# inktime.net
KiCad netlist of a schematic drawn in EAGLE
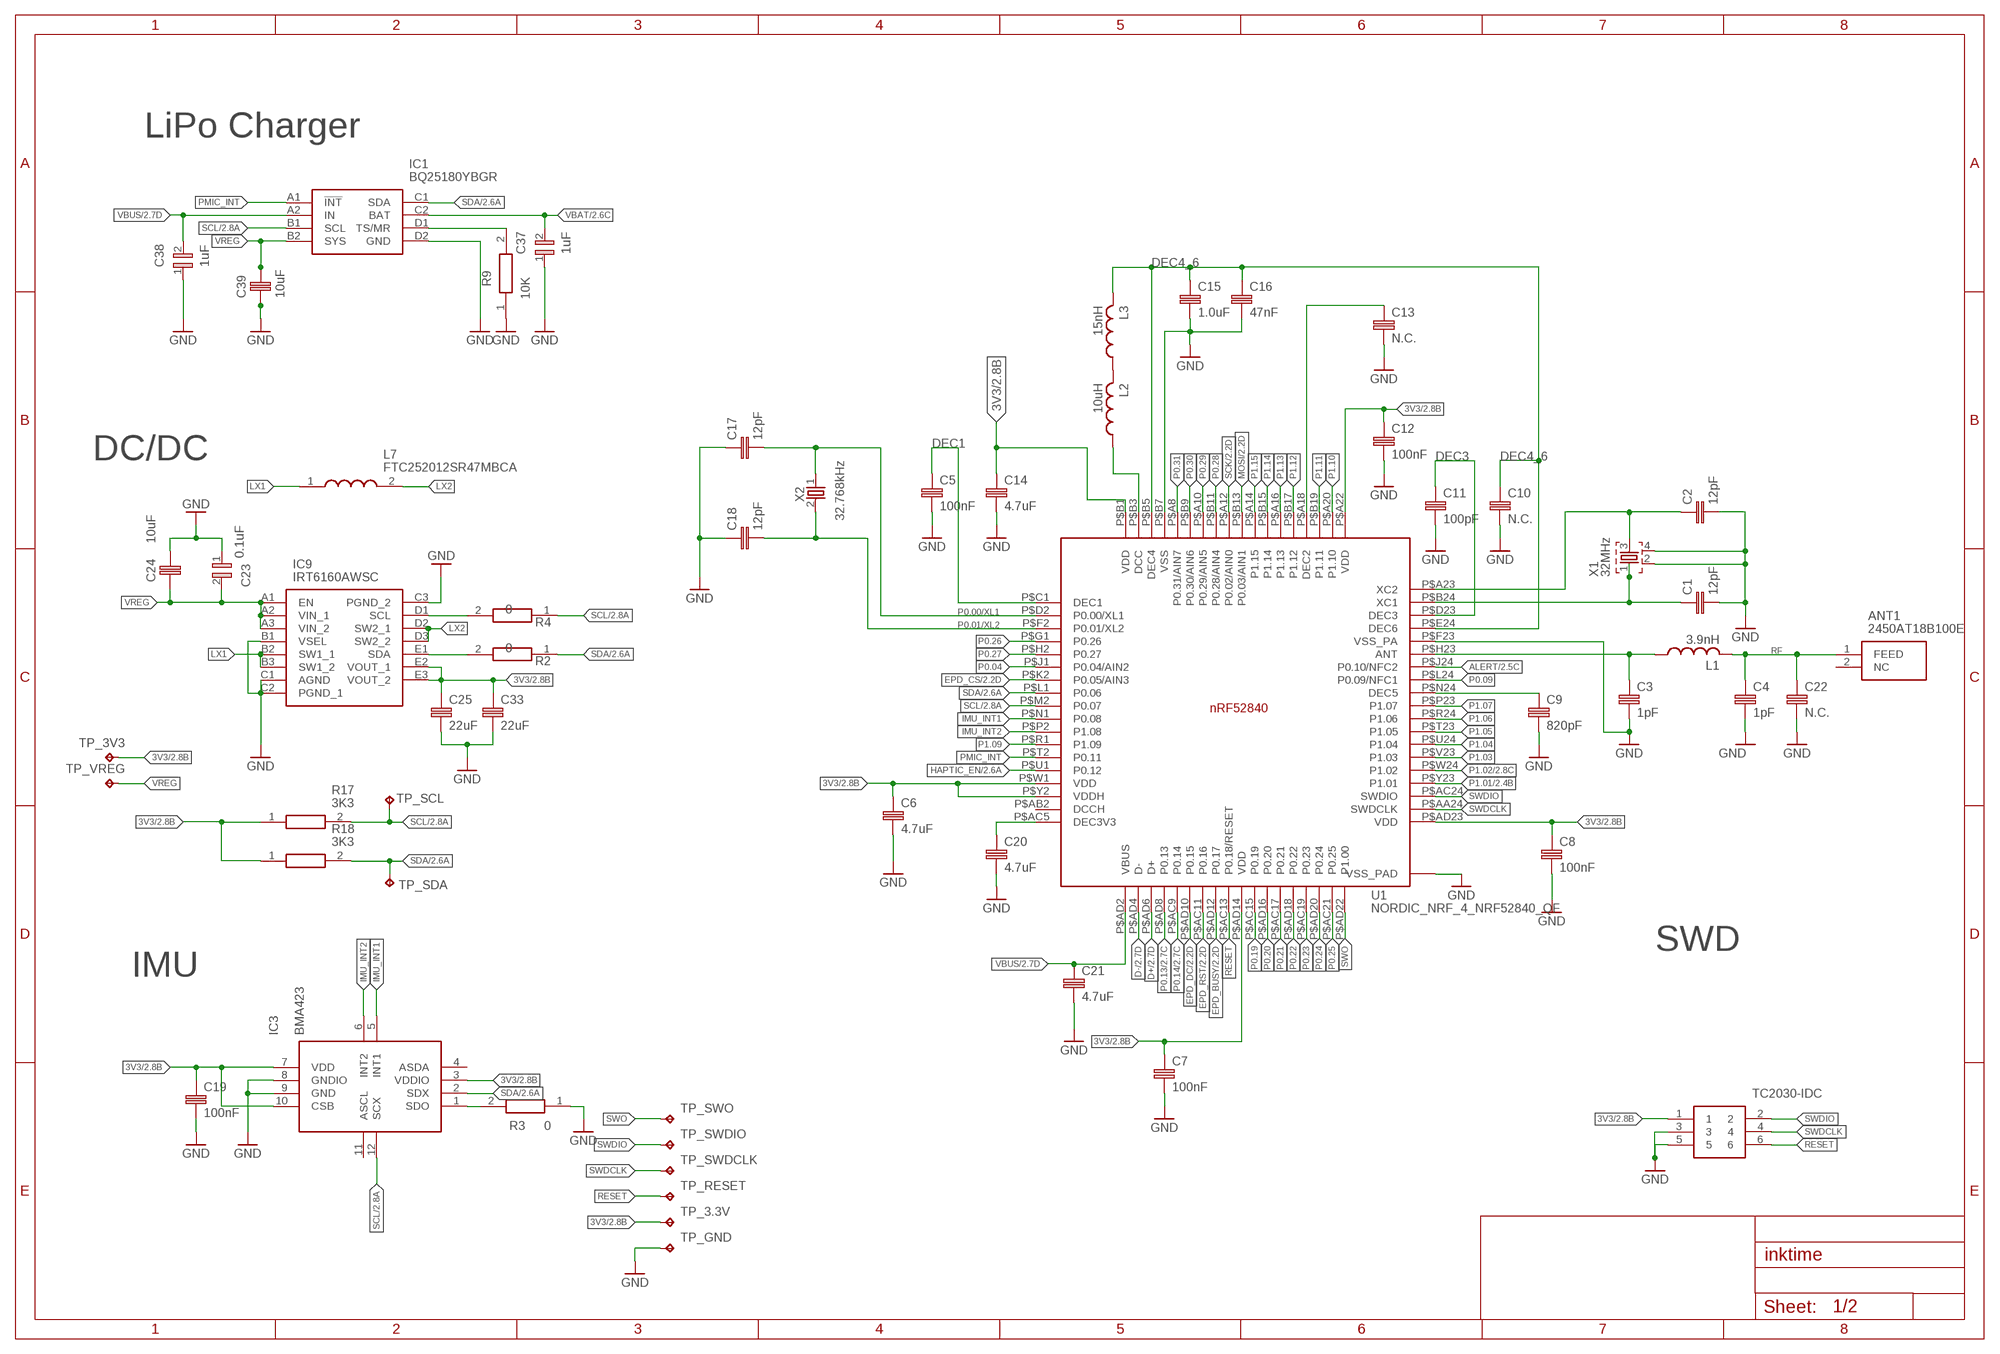
[diagram p0: schematic, sheet 1]
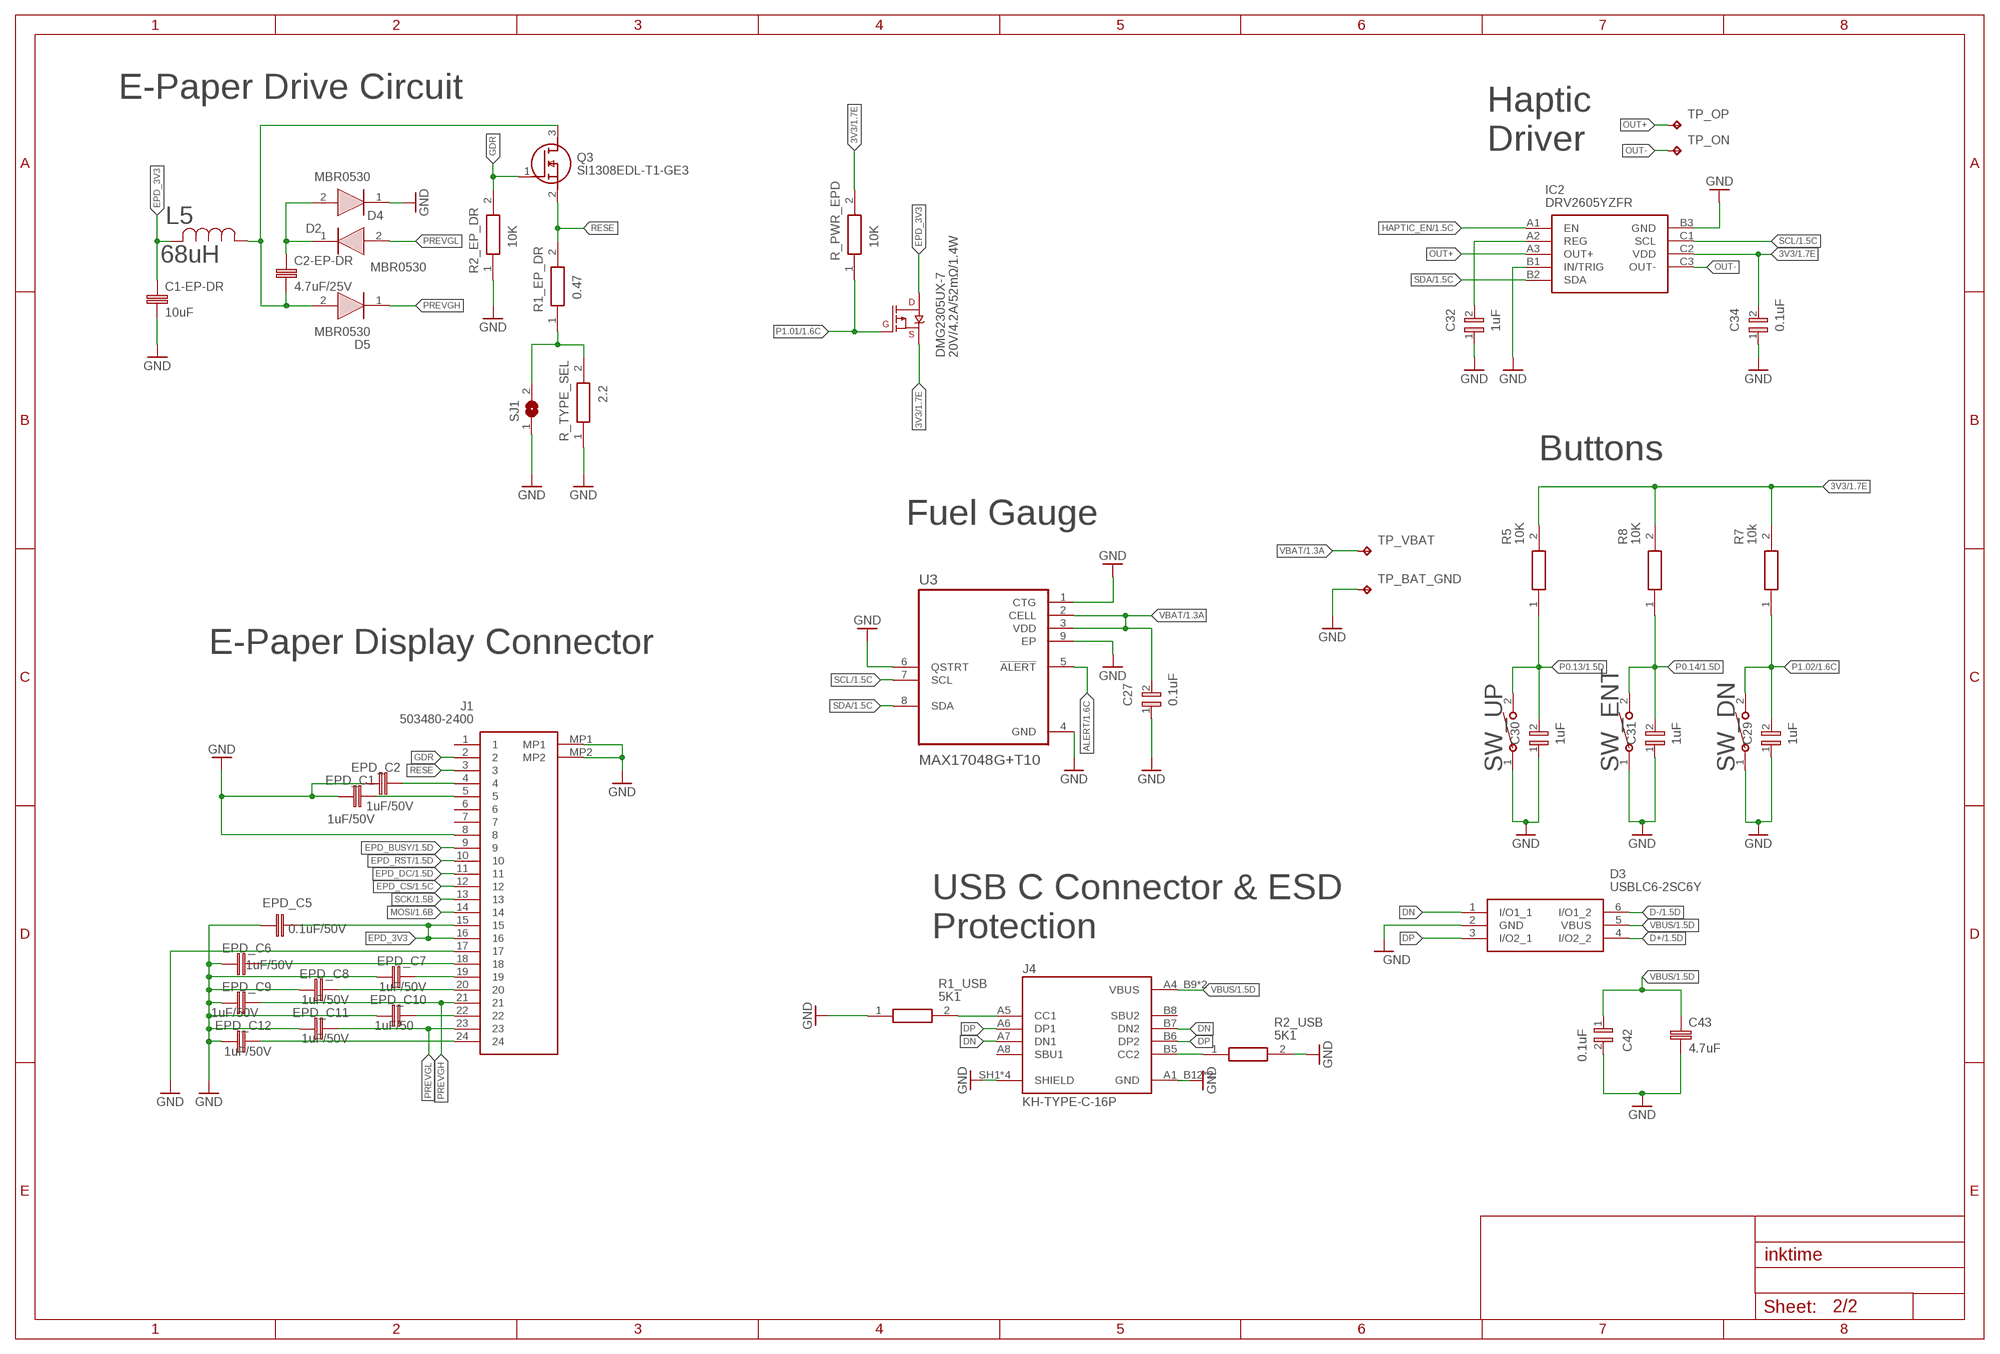
[diagram p1: schematic, sheet 2]

(export (version "E")
  (design (tool "Eeschema 10.0.6"))
  (components
    (comp (ref "ANT1")
      (value "2450AT18B100E")
      (footprint "eagle-import:2450AT18B100E_ANTC3216X140N")
      (fields (field (name "MOUSER_PART_NUMBER") "609-2450AT18B100E"))
      (libsource (lib "eagle-import") (part "2450AT18B100E_2450AT18B100E"))
    )
    (comp (ref "C1")
      (value "12pF")
      (footprint "eagle-import:NORDIC_NRF_3_RESC0201_L")
      (libsource (lib "eagle-import") (part "NORDIC_NRF_3_CAPACITOR_0201_L"))
    )
    (comp (ref "C2")
      (value "12pF")
      (footprint "eagle-import:NORDIC_NRF_3_RESC0201_L")
      (libsource (lib "eagle-import") (part "NORDIC_NRF_3_CAPACITOR_0201_L"))
    )
    (comp (ref "C3")
      (value "1pF")
      (footprint "eagle-import:NORDIC_NRF_3_RESC0201_L")
      (libsource (lib "eagle-import") (part "NORDIC_NRF_3_CAPACITOR_0201_L"))
    )
    (comp (ref "C4")
      (value "1pF")
      (footprint "eagle-import:NORDIC_NRF_3_RESC0201_L")
      (libsource (lib "eagle-import") (part "NORDIC_NRF_3_CAPACITOR_0201_L"))
    )
    (comp (ref "C5")
      (value "100nF")
      (footprint "eagle-import:NORDIC_NRF_3_RESC0201_L")
      (libsource (lib "eagle-import") (part "NORDIC_NRF_3_CAPACITOR_0201_L"))
    )
    (comp (ref "C6")
      (value "4.7uF")
      (footprint "eagle-import:NORDIC_NRF_3_RESC0402_L")
      (libsource (lib "eagle-import") (part "NORDIC_NRF_3_CAPACITOR_0402_L"))
    )
    (comp (ref "C7")
      (value "100nF")
      (footprint "eagle-import:NORDIC_NRF_3_RESC0201_L")
      (libsource (lib "eagle-import") (part "NORDIC_NRF_3_CAPACITOR_0201_L"))
    )
    (comp (ref "C8")
      (value "100nF")
      (footprint "eagle-import:NORDIC_NRF_3_RESC0201_L")
      (libsource (lib "eagle-import") (part "NORDIC_NRF_3_CAPACITOR_0201_L"))
    )
    (comp (ref "C9")
      (value "820pF")
      (footprint "eagle-import:NORDIC_NRF_3_RESC0201_L")
      (libsource (lib "eagle-import") (part "NORDIC_NRF_3_CAPACITOR_0201_L"))
    )
    (comp (ref "C10")
      (value "N.C.")
      (footprint "eagle-import:NORDIC_NRF_3_RESC0201_L")
      (libsource (lib "eagle-import") (part "NORDIC_NRF_3_CAPACITOR_0201_L"))
    )
    (comp (ref "C11")
      (value "100pF")
      (footprint "eagle-import:NORDIC_NRF_3_RESC0201_L")
      (libsource (lib "eagle-import") (part "NORDIC_NRF_3_CAPACITOR_0201_L"))
    )
    (comp (ref "C12")
      (value "100nF")
      (footprint "eagle-import:NORDIC_NRF_3_RESC0201_L")
      (libsource (lib "eagle-import") (part "NORDIC_NRF_3_CAPACITOR_0201_L"))
    )
    (comp (ref "C13")
      (value "N.C.")
      (footprint "eagle-import:NORDIC_NRF_3_RESC0201_L")
      (libsource (lib "eagle-import") (part "NORDIC_NRF_3_CAPACITOR_0201_L"))
    )
    (comp (ref "C14")
      (value "4.7uF")
      (footprint "eagle-import:NORDIC_NRF_3_RESC0402_L")
      (libsource (lib "eagle-import") (part "NORDIC_NRF_3_CAPACITOR_0402_L"))
    )
    (comp (ref "C15")
      (value "1.0uF")
      (footprint "eagle-import:NORDIC_NRF_3_RESC0402_L")
      (libsource (lib "eagle-import") (part "NORDIC_NRF_3_CAPACITOR_0402_L"))
    )
    (comp (ref "C16")
      (value "47nF")
      (footprint "eagle-import:NORDIC_NRF_3_RESC0201_L")
      (libsource (lib "eagle-import") (part "NORDIC_NRF_3_CAPACITOR_0201_L"))
    )
    (comp (ref "C17")
      (value "12pF")
      (footprint "eagle-import:NORDIC_NRF_3_RESC0201_L")
      (libsource (lib "eagle-import") (part "NORDIC_NRF_3_CAPACITOR_0201_L"))
    )
    (comp (ref "C18")
      (value "12pF")
      (footprint "eagle-import:NORDIC_NRF_3_RESC0201_L")
      (libsource (lib "eagle-import") (part "NORDIC_NRF_3_CAPACITOR_0201_L"))
    )
    (comp (ref "C19")
      (value "100nF")
      (footprint "eagle-import:NORDIC_NRF_3_RESC0201_L")
      (libsource (lib "eagle-import") (part "NORDIC_NRF_3_CAPACITOR_0201_L"))
    )
    (comp (ref "C20")
      (value "4.7uF")
      (footprint "eagle-import:NORDIC_NRF_3_RESC0402_L")
      (libsource (lib "eagle-import") (part "NORDIC_NRF_3_CAPACITOR_0402_L"))
    )
    (comp (ref "C21")
      (value "4.7uF")
      (footprint "eagle-import:NORDIC_NRF_3_RESC0402_L")
      (libsource (lib "eagle-import") (part "NORDIC_NRF_3_CAPACITOR_0402_L"))
    )
    (comp (ref "C22")
      (value "N.C.")
      (footprint "eagle-import:NORDIC_NRF_3_RESC0201_L")
      (libsource (lib "eagle-import") (part "NORDIC_NRF_3_CAPACITOR_0201_L"))
    )
    (comp (ref "C23")
      (value "0.1uF")
      (footprint "eagle-import:GRM011R60J152KE01L_2_CAPC0201X13N")
      (fields (field (name "MF") "Murata") (field (name "MP") "GRM011R60J152KE01L"))
      (libsource (lib "eagle-import") (part "GRM011R60J152KE01L_2_GRM011R60J152KE01L"))
    )
    (comp (ref "C24")
      (value "10uF")
      (footprint "eagle-import:NORDIC_NRF_3_RESC0402_L")
      (libsource (lib "eagle-import") (part "NORDIC_NRF_3_CAPACITOR_0402_L"))
    )
    (comp (ref "C25")
      (value "22uF")
      (footprint "eagle-import:NORDIC_NRF_3_RESC0402_L")
      (libsource (lib "eagle-import") (part "NORDIC_NRF_3_CAPACITOR_0402_L"))
    )
    (comp (ref "C33")
      (value "22uF")
      (footprint "eagle-import:NORDIC_NRF_3_RESC0402_L")
      (libsource (lib "eagle-import") (part "NORDIC_NRF_3_CAPACITOR_0402_L"))
    )
    (comp (ref "C37")
      (value "1uF")
      (footprint "eagle-import:GRM011R60J152KE01L_2_CAPC0201X13N")
      (fields (field (name "MF") "Murata") (field (name "MP") "GRM011R60J152KE01L"))
      (libsource (lib "eagle-import") (part "GRM011R60J152KE01L_2_GRM011R60J152KE01L"))
    )
    (comp (ref "C38")
      (value "1uF")
      (footprint "eagle-import:GRM011R60J152KE01L_2_CAPC0201X13N")
      (fields (field (name "MF") "Murata") (field (name "MP") "GRM011R60J152KE01L"))
      (libsource (lib "eagle-import") (part "GRM011R60J152KE01L_2_GRM011R60J152KE01L"))
    )
    (comp (ref "C39")
      (value "10uF")
      (footprint "eagle-import:NORDIC_NRF_3_RESC0402_L")
      (libsource (lib "eagle-import") (part "NORDIC_NRF_3_CAPACITOR_0402_L"))
    )
    (comp (ref "IC1")
      (value "BQ25180YBGR")
      (footprint "eagle-import:BQ25180YBGR_BGA8C40P2X4_100X155X50")
      (fields (field (name "MOUSER_PART_NUMBER") "595-BQ25180YBGR"))
      (libsource (lib "eagle-import") (part "BQ25180YBGR_BQ25180YBGR"))
    )
    (comp (ref "IC3")
      (value "BMA423")
      (footprint "eagle-import:BMA423_BMA423")
      (fields (field (name "MOUSER_PART_NUMBER") "262-BMA423"))
      (libsource (lib "eagle-import") (part "BMA423_BMA423"))
    )
    (comp (ref "IC9")
      (value "IRT6160AWSC")
      (footprint "eagle-import:RT6160AWSC_BGA15C40P3X5_140X230X60")
      (fields
        (field (name "MANUFACTURER_PART_NUMBER") "RT6160AWSC")
        (field (name "MOUSER_PART_NUMBER") "835-RT6160AWSC")
      )
      (libsource (lib "eagle-import") (part "RT6160AWSC_RT6160AWSC"))
    )
    (comp (ref "J2")
      (value "TC2030-IDC")
      (footprint "eagle-import:TC2030-IDC_TC2030IDC")
      (libsource (lib "eagle-import") (part "TC2030-IDC_TC2030-IDC"))
    )
    (comp (ref "L1")
      (value "3.9nH")
      (footprint "eagle-import:NORDIC_NRF_2_RESC0402_L")
      (libsource (lib "eagle-import") (part "NORDIC_NRF_2_INDUCTOR_0402_L"))
    )
    (comp (ref "L2")
      (value "10uH")
      (footprint "eagle-import:NORDIC_NRF_2_RESC0402_L")
      (libsource (lib "eagle-import") (part "NORDIC_NRF_2_INDUCTOR_0402_L"))
    )
    (comp (ref "L3")
      (value "15nH")
      (footprint "eagle-import:NORDIC_NRF_2_RESC0402_L")
      (libsource (lib "eagle-import") (part "NORDIC_NRF_2_INDUCTOR_0402_L"))
    )
    (comp (ref "L7")
      (value "FTC252012SR47MBCA")
      (footprint "eagle-import:MLP2016SR47MT0S1_INDC2016X100N")
      (libsource (lib "eagle-import") (part "MLP2016SR47MT0S1_FTC252012SR47MBCA"))
    )
    (comp (ref "R2")
      (value "0")
      (footprint "eagle-import:ERA-1AEB3401C_0201")
      (libsource (lib "eagle-import") (part "ERA-1AEB3401C_CPF0201D7K68C1"))
    )
    (comp (ref "R3")
      (value "0")
      (footprint "eagle-import:CPF0201D7K68C1_0201")
      (libsource (lib "eagle-import") (part "CPF0201D7K68C1_CPF0201D7K68C1"))
    )
    (comp (ref "R4")
      (value "0")
      (footprint "eagle-import:ERA-1AEB3401C_0201")
      (libsource (lib "eagle-import") (part "ERA-1AEB3401C_CPF0201D7K68C1"))
    )
    (comp (ref "R9")
      (value "10K")
      (footprint "eagle-import:ERA-1AEB3401C_0201")
      (libsource (lib "eagle-import") (part "ERA-1AEB3401C_CPF0201D7K68C1"))
    )
    (comp (ref "R17")
      (value "3K3")
      (footprint "eagle-import:CPF0201D7K68C1_0201")
      (libsource (lib "eagle-import") (part "CPF0201D7K68C1_CPF0201D7K68C1"))
    )
    (comp (ref "R18")
      (value "3K3")
      (footprint "eagle-import:CPF0201D7K68C1_0201")
      (libsource (lib "eagle-import") (part "CPF0201D7K68C1_CPF0201D7K68C1"))
    )
    (comp (ref "TP_3.3V")
      (value "HECTOR_WATCH_1_TPTP20R")
      (footprint "eagle-import:HECTOR_WATCH_1_TP20R")
      (libsource (lib "eagle-import") (part "HECTOR_WATCH_1_TPTP20R"))
    )
    (comp (ref "TP_3V3")
      (value "HECTOR_WATCH_1_TPTP20R")
      (footprint "eagle-import:HECTOR_WATCH_1_TP20R")
      (libsource (lib "eagle-import") (part "HECTOR_WATCH_1_TPTP20R"))
    )
    (comp (ref "TP_GND")
      (value "HECTOR_WATCH_1_TPTP20R")
      (footprint "eagle-import:HECTOR_WATCH_1_TP20R")
      (libsource (lib "eagle-import") (part "HECTOR_WATCH_1_TPTP20R"))
    )
    (comp (ref "TP_RESET")
      (value "HECTOR_WATCH_1_TPTP20R")
      (footprint "eagle-import:HECTOR_WATCH_1_TP20R")
      (libsource (lib "eagle-import") (part "HECTOR_WATCH_1_TPTP20R"))
    )
    (comp (ref "TP_SCL")
      (value "HECTOR_WATCH_1_TPTP20R")
      (footprint "eagle-import:HECTOR_WATCH_1_TP20R")
      (libsource (lib "eagle-import") (part "HECTOR_WATCH_1_TPTP20R"))
    )
    (comp (ref "TP_SDA")
      (value "HECTOR_WATCH_1_TPTP20R")
      (footprint "eagle-import:HECTOR_WATCH_1_TP20R")
      (libsource (lib "eagle-import") (part "HECTOR_WATCH_1_TPTP20R"))
    )
    (comp (ref "TP_SWDCLK")
      (value "HECTOR_WATCH_1_TPTP20R")
      (footprint "eagle-import:HECTOR_WATCH_1_TP20R")
      (libsource (lib "eagle-import") (part "HECTOR_WATCH_1_TPTP20R"))
    )
    (comp (ref "TP_SWDIO")
      (value "HECTOR_WATCH_1_TPTP20R")
      (footprint "eagle-import:HECTOR_WATCH_1_TP20R")
      (libsource (lib "eagle-import") (part "HECTOR_WATCH_1_TPTP20R"))
    )
    (comp (ref "TP_SWO")
      (value "HECTOR_WATCH_1_TPTP20R")
      (footprint "eagle-import:HECTOR_WATCH_1_TP20R")
      (libsource (lib "eagle-import") (part "HECTOR_WATCH_1_TPTP20R"))
    )
    (comp (ref "TP_VREG")
      (value "HECTOR_WATCH_1_TPTP20R")
      (footprint "eagle-import:HECTOR_WATCH_1_TP20R")
      (libsource (lib "eagle-import") (part "HECTOR_WATCH_1_TPTP20R"))
    )
    (comp (ref "U$3")
      (value "NORDIC_NRF_3_CAPACITOR_0402_L")
      (footprint "eagle-import:NORDIC_NRF_3_RESC0402_L")
      (libsource (lib "eagle-import") (part "NORDIC_NRF_3_CAPACITOR_0402_L"))
    )
    (comp (ref "U1")
      (value "NORDIC_NRF_4_NRF52840_QF")
      (footprint "eagle-import:NORDIC_NRF_4_AQFN50P700X700X85_HS-74N")
      (libsource (lib "eagle-import") (part "NORDIC_NRF_4_NRF52840_QF"))
    )
    (comp (ref "X1")
      (value "32MHz")
      (footprint "eagle-import:NORDIC_NRF_BT-XTAL_2016_N")
      (libsource (lib "eagle-import") (part "NORDIC_NRF_XTAL_32MHZ"))
    )
    (comp (ref "X2")
      (value "32.768kHz")
      (footprint "eagle-import:NORDIC_NRF_1_XTAL_3215_N")
      (libsource (lib "eagle-import") (part "NORDIC_NRF_1_XTAL_32KHZ"))
    )
    (comp (ref "C1-EP-DR")
      (value "10uF")
      (footprint "eagle-import:NORDIC_NRF_3_RESC0402_L")
      (libsource (lib "eagle-import") (part "NORDIC_NRF_3_CAPACITOR_0402_L"))
    )
    (comp (ref "C2-EP-DR")
      (value "4.7uF/25V")
      (footprint "eagle-import:NORDIC_NRF_3_RESC0402_L")
      (libsource (lib "eagle-import") (part "NORDIC_NRF_3_CAPACITOR_0402_L"))
    )
    (comp (ref "C27")
      (value "0.1uF")
      (footprint "eagle-import:GRM011R60J152KE01L_2_CAPC0201X13N")
      (fields (field (name "MF") "Murata") (field (name "MP") "GRM011R60J152KE01L"))
      (libsource (lib "eagle-import") (part "GRM011R60J152KE01L_2_GRM011R60J152KE01L"))
    )
    (comp (ref "C29")
      (value "1uF")
      (footprint "eagle-import:GRM011R60J152KE01L_2_CAPC0201X13N")
      (fields (field (name "MF") "Murata") (field (name "MP") "GRM011R60J152KE01L"))
      (libsource (lib "eagle-import") (part "GRM011R60J152KE01L_2_GRM011R60J152KE01L"))
    )
    (comp (ref "C30")
      (value "1uF")
      (footprint "eagle-import:GRM011R60J152KE01L_2_CAPC0201X13N")
      (fields (field (name "MF") "Murata") (field (name "MP") "GRM011R60J152KE01L"))
      (libsource (lib "eagle-import") (part "GRM011R60J152KE01L_2_GRM011R60J152KE01L"))
    )
    (comp (ref "C31")
      (value "1uF")
      (footprint "eagle-import:GRM011R60J152KE01L_2_CAPC0201X13N")
      (fields (field (name "MF") "Murata") (field (name "MP") "GRM011R60J152KE01L"))
      (libsource (lib "eagle-import") (part "GRM011R60J152KE01L_2_GRM011R60J152KE01L"))
    )
    (comp (ref "C32")
      (value "1uF")
      (footprint "eagle-import:GRM011R60J152KE01L_2_CAPC0201X13N")
      (fields (field (name "MF") "Murata") (field (name "MP") "GRM011R60J152KE01L"))
      (libsource (lib "eagle-import") (part "GRM011R60J152KE01L_2_GRM011R60J152KE01L"))
    )
    (comp (ref "C34")
      (value "0.1uF")
      (footprint "eagle-import:GRM011R60J152KE01L_2_CAPC0201X13N")
      (fields (field (name "MF") "Murata") (field (name "MP") "GRM011R60J152KE01L"))
      (libsource (lib "eagle-import") (part "GRM011R60J152KE01L_2_GRM011R60J152KE01L"))
    )
    (comp (ref "C42")
      (value "0.1uF")
      (footprint "eagle-import:GRM011R60J152KE01L_2_CAPC0201X13N")
      (fields (field (name "MF") "Murata") (field (name "MP") "GRM011R60J152KE01L"))
      (libsource (lib "eagle-import") (part "GRM011R60J152KE01L_2_GRM011R60J152KE01L"))
    )
    (comp (ref "C43")
      (value "4.7uF")
      (footprint "eagle-import:NORDIC_NRF_3_RESC0402_L")
      (libsource (lib "eagle-import") (part "NORDIC_NRF_3_CAPACITOR_0402_L"))
    )
    (comp (ref "D2")
      (value "MBR0530")
      (footprint "eagle-import:ESP32_C6_LIBRARY_5_SOD3716X135N")
      (fields (field (name "MF") "ON Semiconductor"))
      (libsource (lib "eagle-import") (part "ESP32_C6_LIBRARY_5_MBR0530"))
    )
    (comp (ref "D3")
      (value "USBLC6-2SC6Y")
      (footprint "eagle-import:ESP32_C6_LIBRARY_3_SOT95P280X145-6N")
      (fields (field (name "MF") "STMicroelectronics"))
      (libsource (lib "eagle-import") (part "ESP32_C6_LIBRARY_3_USBLC6-2SC6Y"))
    )
    (comp (ref "D4")
      (value "MBR0530")
      (footprint "eagle-import:ESP32_C6_LIBRARY_5_SOD3716X135N")
      (fields (field (name "MF") "ON Semiconductor"))
      (libsource (lib "eagle-import") (part "ESP32_C6_LIBRARY_5_MBR0530"))
    )
    (comp (ref "D5")
      (value "MBR0530")
      (footprint "eagle-import:ESP32_C6_LIBRARY_5_SOD3716X135N")
      (fields (field (name "MF") "ON Semiconductor"))
      (libsource (lib "eagle-import") (part "ESP32_C6_LIBRARY_5_MBR0530"))
    )
    (comp (ref "DMG2305UX-7")
      (value "20V/4.2A/52mΩ/1.4W")
      (footprint "eagle-import:ESP32_C6_LIBRARY_4_ESP32_C6_LIBRARY_4_ESP32_C6_LIBRARY_4_ESP32_C6_LIBRARY_4_ESP32_WROVER_SPARKFUN-DISCRETESEMI_SOT23-3")
      (libsource (lib "eagle-import") (part "ESP32_C6_LIBRARY_4_ESP32_WROVER_SPARKFUN-DISCRETESEMI_MOSFET_PCH-DMG2305UX-7"))
    )
    (comp (ref "EPD_C1")
      (value "1uF/50V")
      (footprint "eagle-import:NORDIC_NRF_3_RESC0402_L")
      (libsource (lib "eagle-import") (part "NORDIC_NRF_3_CAPACITOR_0402_L"))
    )
    (comp (ref "EPD_C2")
      (value "1uF/50V")
      (footprint "eagle-import:NORDIC_NRF_3_RESC0402_L")
      (libsource (lib "eagle-import") (part "NORDIC_NRF_3_CAPACITOR_0402_L"))
    )
    (comp (ref "EPD_C5")
      (value "0.1uF/50V")
      (footprint "eagle-import:NORDIC_NRF_3_RESC0201_L")
      (libsource (lib "eagle-import") (part "NORDIC_NRF_3_CAPACITOR_0201_L"))
    )
    (comp (ref "EPD_C6")
      (value "1uF/50V")
      (footprint "eagle-import:NORDIC_NRF_3_RESC0402_L")
      (libsource (lib "eagle-import") (part "NORDIC_NRF_3_CAPACITOR_0402_L"))
    )
    (comp (ref "EPD_C7")
      (value "1uF/50V")
      (footprint "eagle-import:NORDIC_NRF_3_RESC0402_L")
      (libsource (lib "eagle-import") (part "NORDIC_NRF_3_CAPACITOR_0402_L"))
    )
    (comp (ref "EPD_C8")
      (value "1uF/50V")
      (footprint "eagle-import:NORDIC_NRF_3_RESC0402_L")
      (libsource (lib "eagle-import") (part "NORDIC_NRF_3_CAPACITOR_0402_L"))
    )
    (comp (ref "EPD_C9")
      (value "1uF/50V")
      (footprint "eagle-import:NORDIC_NRF_3_RESC0402_L")
      (libsource (lib "eagle-import") (part "NORDIC_NRF_3_CAPACITOR_0402_L"))
    )
    (comp (ref "EPD_C10")
      (value "1uF/50")
      (footprint "eagle-import:NORDIC_NRF_3_RESC0402_L")
      (libsource (lib "eagle-import") (part "NORDIC_NRF_3_CAPACITOR_0402_L"))
    )
    (comp (ref "EPD_C11")
      (value "1uF/50V")
      (footprint "eagle-import:NORDIC_NRF_3_RESC0402_L")
      (libsource (lib "eagle-import") (part "NORDIC_NRF_3_CAPACITOR_0402_L"))
    )
    (comp (ref "EPD_C12")
      (value "1uF/50V")
      (footprint "eagle-import:NORDIC_NRF_3_RESC0402_L")
      (libsource (lib "eagle-import") (part "NORDIC_NRF_3_CAPACITOR_0402_L"))
    )
    (comp (ref "IC2")
      (value "DRV2605YZFR")
      (footprint "eagle-import:DRV2605YZFR_BGA9C50P3X3_144X144X62")
      (libsource (lib "eagle-import") (part "DRV2605YZFR_DRV2605YZFR"))
    )
    (comp (ref "J1")
      (value "503480-2400")
      (footprint "eagle-import:503480-2400_5034802400")
      (fields (field (name "MOUSER_PART_NUMBER") "538-503480-2400"))
      (libsource (lib "eagle-import") (part "503480-2400_503480-2400"))
    )
    (comp (ref "J4")
      (value "KH-TYPE-C-16P")
      (footprint "eagle-import:KH-TYPE-C-16P_KINGHELM_KH-TYPE-C-16P")
      (fields (field (name "MF") "kinghelm"))
      (libsource (lib "eagle-import") (part "KH-TYPE-C-16P_KH-TYPE-C-16P"))
    )
    (comp (ref "L5")
      (value "68uH")
      (footprint "eagle-import:ESP32_C6_LIBRARY_2_IND_4828-WE-TPC_WRE")
      (fields
        (field (name "MANUFACTURER_PART_NUMBER") "744043680")
        (field (name "COPYRIGHT") "Copyright (C) 2024 Ultra Librarian. All rights reserved.")
      )
      (libsource (lib "eagle-import") (part "ESP32_C6_LIBRARY_2_744043680IND_4828-WE-TPC_WRE"))
    )
    (comp (ref "Q3")
      (value "SI1308EDL-T1-GE3")
      (footprint "eagle-import:ESP32_C6_LIBRARY_6_SOT65P210X110-3N")
      (fields (field (name "MF") "Vishay Siliconix"))
      (libsource (lib "eagle-import") (part "ESP32_C6_LIBRARY_6_SI1308EDL-T1-GE3"))
    )
    (comp (ref "R1_EP_DR")
      (value "0.47")
      (footprint "eagle-import:ERA-1AEB3401C_0201")
      (libsource (lib "eagle-import") (part "ERA-1AEB3401C_CPF0201D7K68C1"))
    )
    (comp (ref "R1_USB")
      (value "5K1")
      (footprint "eagle-import:ERA-1AEB3401C_0201")
      (libsource (lib "eagle-import") (part "ERA-1AEB3401C_CPF0201D7K68C1"))
    )
    (comp (ref "R2_EP_DR")
      (value "10K")
      (footprint "eagle-import:ERA-1AEB3401C_0201")
      (libsource (lib "eagle-import") (part "ERA-1AEB3401C_CPF0201D7K68C1"))
    )
    (comp (ref "R2_USB")
      (value "5K1")
      (footprint "eagle-import:ERA-1AEB3401C_0201")
      (libsource (lib "eagle-import") (part "ERA-1AEB3401C_CPF0201D7K68C1"))
    )
    (comp (ref "R5")
      (value "10K")
      (footprint "eagle-import:ERA-1AEB3401C_0201")
      (libsource (lib "eagle-import") (part "ERA-1AEB3401C_CPF0201D7K68C1"))
    )
    (comp (ref "R7")
      (value "10k")
      (footprint "eagle-import:ERA-1AEB3401C_0201")
      (libsource (lib "eagle-import") (part "ERA-1AEB3401C_CPF0201D7K68C1"))
    )
    (comp (ref "R8")
      (value "10K")
      (footprint "eagle-import:ERA-1AEB3401C_0201")
      (libsource (lib "eagle-import") (part "ERA-1AEB3401C_CPF0201D7K68C1"))
    )
    (comp (ref "R_PWR_EPD")
      (value "10K")
      (footprint "eagle-import:ERA-1AEB3401C_0201")
      (libsource (lib "eagle-import") (part "ERA-1AEB3401C_CPF0201D7K68C1"))
    )
    (comp (ref "R_TYPE_SEL")
      (value "2.2")
      (footprint "eagle-import:ERA-1AEB3401C_0201")
      (libsource (lib "eagle-import") (part "ERA-1AEB3401C_CPF0201D7K68C1"))
    )
    (comp (ref "SJ1")
      (value "ESP32_C6_LIBRARY_7_JUMPER_SJ")
      (footprint "eagle-import:ESP32_C6_LIBRARY_7_JUMPER_SJ")
      (libsource (lib "eagle-import") (part "ESP32_C6_LIBRARY_7_JUMPER_SJ"))
    )
    (comp (ref "SW_DN")
      (value "2025-10-22_07-23-44_LIBRARY_EVP-AKE31ASW_EVP-AKE31A_PAN")
      (footprint "eagle-import:2025-10-22_07-23-44_LIBRARY_SW_EVP-AKE31A_PAN")
      (fields
        (field (name "MANUFACTURER_PART_NUMBER") "EVP-AKE31A")
        (field (name "COPYRIGHT") "Copyright (C) 2025 Ultra Librarian. All rights reserved.")
      )
      (libsource (lib "eagle-import") (part "2025-10-22_07-23-44_LIBRARY_EVP-AKE31ASW_EVP-AKE31A_PAN"))
    )
    (comp (ref "SW_ENT")
      (value "2025-10-22_07-23-44_LIBRARY_EVP-AKE31ASW_EVP-AKE31A_PAN")
      (footprint "eagle-import:2025-10-22_07-23-44_LIBRARY_SW_EVP-AKE31A_PAN")
      (fields
        (field (name "MANUFACTURER_PART_NUMBER") "EVP-AKE31A")
        (field (name "COPYRIGHT") "Copyright (C) 2025 Ultra Librarian. All rights reserved.")
      )
      (libsource (lib "eagle-import") (part "2025-10-22_07-23-44_LIBRARY_EVP-AKE31ASW_EVP-AKE31A_PAN"))
    )
    (comp (ref "SW_UP")
      (value "2025-10-22_07-23-44_LIBRARY_EVP-AKE31ASW_EVP-AKE31A_PAN")
      (footprint "eagle-import:2025-10-22_07-23-44_LIBRARY_SW_EVP-AKE31A_PAN")
      (fields
        (field (name "MANUFACTURER_PART_NUMBER") "EVP-AKE31A")
        (field (name "COPYRIGHT") "Copyright (C) 2025 Ultra Librarian. All rights reserved.")
      )
      (libsource (lib "eagle-import") (part "2025-10-22_07-23-44_LIBRARY_EVP-AKE31ASW_EVP-AKE31A_PAN"))
    )
    (comp (ref "TP_BAT_GND")
      (value "HECTOR_WATCH_1_TPTP20R")
      (footprint "eagle-import:HECTOR_WATCH_1_TP20R")
      (libsource (lib "eagle-import") (part "HECTOR_WATCH_1_TPTP20R"))
    )
    (comp (ref "TP_ON")
      (value "HECTOR_WATCH_1_TPTP20R")
      (footprint "eagle-import:HECTOR_WATCH_1_TP20R")
      (libsource (lib "eagle-import") (part "HECTOR_WATCH_1_TPTP20R"))
    )
    (comp (ref "TP_OP")
      (value "HECTOR_WATCH_1_TPTP20R")
      (footprint "eagle-import:HECTOR_WATCH_1_TP20R")
      (libsource (lib "eagle-import") (part "HECTOR_WATCH_1_TPTP20R"))
    )
    (comp (ref "TP_VBAT")
      (value "HECTOR_WATCH_1_TPTP20R")
      (footprint "eagle-import:HECTOR_WATCH_1_TP20R")
      (libsource (lib "eagle-import") (part "HECTOR_WATCH_1_TPTP20R"))
    )
    (comp (ref "U3")
      (value "MAX17048G+T10")
      (footprint "eagle-import:ESP32_C6_LIBRARY_SON50P200X200X80-9N")
      (fields (field (name "MF") "Analog Devices"))
      (libsource (lib "eagle-import") (part "ESP32_C6_LIBRARY_MAX17048G+T10"))
    )
  )
  (nets
    (net (code "1") (name "3V3") (class "Default")
      (node (ref "C12") (pin "1") (pinfunction "1_1") (pintype "passive"))
      (node (ref "C14") (pin "1") (pinfunction "1_1") (pintype "passive"))
      (node (ref "C19") (pin "1") (pinfunction "1_1") (pintype "passive"))
      (node (ref "C25") (pin "1") (pinfunction "1_1") (pintype "passive"))
      (node (ref "C33") (pin "1") (pinfunction "1_1") (pintype "passive"))
      (node (ref "C34") (pin "2") (pinfunction "2_2") (pintype "passive"))
      (node (ref "C6") (pin "1") (pinfunction "1_1") (pintype "passive"))
      (node (ref "C7") (pin "1") (pinfunction "1_1") (pintype "passive"))
      (node (ref "C8") (pin "1") (pinfunction "1_1") (pintype "passive"))
      (node (ref "DMG2305UX-7") (pin "2") (pinfunction "S_2") (pintype "bidirectional"))
      (node (ref "IC2") (pin "C2") (pinfunction "VDD_C2") (pintype "bidirectional"))
      (node (ref "IC3") (pin "10") (pinfunction "CSB_10") (pintype "bidirectional"))
      (node (ref "IC3") (pin "3") (pinfunction "VDDIO_3") (pintype "bidirectional"))
      (node (ref "IC3") (pin "7") (pinfunction "VDD_7") (pintype "bidirectional"))
      (node (ref "IC9") (pin "E2") (pinfunction "VOUT_1_E2") (pintype "bidirectional"))
      (node (ref "IC9") (pin "E3") (pinfunction "VOUT_2_E3") (pintype "bidirectional"))
      (node (ref "J2") (pin "1") (pinfunction "1_1") (pintype "bidirectional"))
      (node (ref "R17") (pin "1") (pinfunction "1_1") (pintype "bidirectional"))
      (node (ref "R18") (pin "1") (pinfunction "1_1") (pintype "bidirectional"))
      (node (ref "R5") (pin "2") (pinfunction "2_2") (pintype "bidirectional"))
      (node (ref "R7") (pin "2") (pinfunction "2_2") (pintype "bidirectional"))
      (node (ref "R8") (pin "2") (pinfunction "2_2") (pintype "bidirectional"))
      (node (ref "R_PWR_EPD") (pin "2") (pinfunction "2_2") (pintype "bidirectional"))
      (node (ref "TP_3.3V") (pin "TP") (pinfunction "TP_TP") (pintype "input"))
      (node (ref "TP_3V3") (pin "TP") (pinfunction "TP_TP") (pintype "input"))
      (node (ref "U1") (pin "P$A22") (pinfunction "VDD_P$A22") (pintype "power_in"))
      (node (ref "U1") (pin "P$AD14") (pinfunction "VDD_P$AD14") (pintype "power_in"))
      (node (ref "U1") (pin "P$AD23") (pinfunction "VDD_P$AD23") (pintype "power_in"))
      (node (ref "U1") (pin "P$B1") (pinfunction "VDD_P$B1") (pintype "power_in"))
      (node (ref "U1") (pin "P$W1") (pinfunction "VDD_P$W1") (pintype "power_in"))
      (node (ref "U1") (pin "P$Y2") (pinfunction "VDDH_P$Y2") (pintype "power_in"))
    )
    (net (code "2") (name "ALERT") (class "Default")
      (node (ref "U1") (pin "P$J24") (pinfunction "P0.10/NFC2_P$J24") (pintype "bidirectional"))
      (node (ref "U3") (pin "5") (pinfunction "~{ALERT}_5") (pintype "output"))
    )
    (net (code "3") (name "D+") (class "Default")
      (node (ref "D3") (pin "4") (pinfunction "I/O2_2_4") (pintype "bidirectional"))
      (node (ref "U1") (pin "P$AD6") (pinfunction "D+_P$AD6") (pintype "bidirectional"))
    )
    (net (code "4") (name "D-") (class "Default")
      (node (ref "D3") (pin "6") (pinfunction "I/O1_2_6") (pintype "bidirectional"))
      (node (ref "U1") (pin "P$AD4") (pinfunction "D-_P$AD4") (pintype "bidirectional"))
    )
    (net (code "5") (name "DEC1") (class "Default")
      (node (ref "C5") (pin "1") (pinfunction "1_1") (pintype "passive"))
      (node (ref "U1") (pin "P$C1") (pinfunction "DEC1_P$C1") (pintype "power_in"))
    )
    (net (code "6") (name "DEC3") (class "Default")
      (node (ref "C11") (pin "1") (pinfunction "1_1") (pintype "passive"))
      (node (ref "U1") (pin "P$D23") (pinfunction "DEC3_P$D23") (pintype "bidirectional"))
    )
    (net (code "7") (name "DEC4_6") (class "Default")
      (node (ref "C10") (pin "1") (pinfunction "1_1") (pintype "passive"))
      (node (ref "C15") (pin "1") (pinfunction "1_1") (pintype "passive"))
      (node (ref "C16") (pin "1") (pinfunction "1_1") (pintype "passive"))
      (node (ref "L3") (pin "2") (pinfunction "2_2") (pintype "passive"))
      (node (ref "U1") (pin "P$B5") (pinfunction "DEC4_P$B5") (pintype "power_in"))
      (node (ref "U1") (pin "P$E24") (pinfunction "DEC6_P$E24") (pintype "bidirectional"))
    )
    (net (code "8") (name "DN") (class "Default")
      (node (ref "D3") (pin "1") (pinfunction "I/O1_1_1") (pintype "bidirectional"))
      (node (ref "J4") (pin "A7") (pinfunction "DN1_A7") (pintype "bidirectional"))
      (node (ref "J4") (pin "B7") (pinfunction "DN2_B7") (pintype "bidirectional"))
    )
    (net (code "9") (name "DP") (class "Default")
      (node (ref "D3") (pin "3") (pinfunction "I/O2_1_3") (pintype "bidirectional"))
      (node (ref "J4") (pin "A6") (pinfunction "DP1_A6") (pintype "bidirectional"))
      (node (ref "J4") (pin "B6") (pinfunction "DP2_B6") (pintype "bidirectional"))
    )
    (net (code "10") (name "EPD_3V3") (class "Default")
      (node (ref "C1-EP-DR") (pin "1") (pinfunction "1_1") (pintype "passive"))
      (node (ref "DMG2305UX-7") (pin "3") (pinfunction "D_3") (pintype "bidirectional"))
      (node (ref "EPD_C5") (pin "1") (pinfunction "1_1") (pintype "passive"))
      (node (ref "J1") (pin "15") (pinfunction "15_15") (pintype "bidirectional"))
      (node (ref "J1") (pin "16") (pinfunction "16_16") (pintype "bidirectional"))
      (node (ref "L5") (pin "2") (pinfunction "2_2") (pintype "passive"))
    )
    (net (code "11") (name "EPD_BUSY") (class "Default")
      (node (ref "J1") (pin "9") (pinfunction "9_9") (pintype "bidirectional"))
      (node (ref "U1") (pin "P$AD12") (pinfunction "P0.17_P$AD12") (pintype "bidirectional"))
    )
    (net (code "12") (name "EPD_CS") (class "Default")
      (node (ref "J1") (pin "12") (pinfunction "12_12") (pintype "bidirectional"))
      (node (ref "U1") (pin "P$K2") (pinfunction "P0.05/AIN3_P$K2") (pintype "bidirectional"))
    )
    (net (code "13") (name "EPD_DC") (class "Default")
      (node (ref "J1") (pin "11") (pinfunction "11_11") (pintype "bidirectional"))
      (node (ref "U1") (pin "P$AD10") (pinfunction "P0.15_P$AD10") (pintype "bidirectional"))
    )
    (net (code "14") (name "EPD_RST") (class "Default")
      (node (ref "J1") (pin "10") (pinfunction "10_10") (pintype "bidirectional"))
      (node (ref "U1") (pin "P$AC11") (pinfunction "P0.16_P$AC11") (pintype "bidirectional"))
    )
    (net (code "15") (name "GDR") (class "Default")
      (node (ref "J1") (pin "2") (pinfunction "2_2") (pintype "bidirectional"))
      (node (ref "Q3") (pin "1") (pinfunction "G_1") (pintype "bidirectional"))
      (node (ref "R2_EP_DR") (pin "2") (pinfunction "2_2") (pintype "bidirectional"))
    )
    (net (code "16") (name "GND") (class "Default")
      (node (ref "C1") (pin "2") (pinfunction "2_2") (pintype "passive"))
      (node (ref "C1-EP-DR") (pin "2") (pinfunction "2_2") (pintype "passive"))
      (node (ref "C10") (pin "2") (pinfunction "2_2") (pintype "passive"))
      (node (ref "C11") (pin "2") (pinfunction "2_2") (pintype "passive"))
      (node (ref "C12") (pin "2") (pinfunction "2_2") (pintype "passive"))
      (node (ref "C13") (pin "2") (pinfunction "2_2") (pintype "passive"))
      (node (ref "C14") (pin "2") (pinfunction "2_2") (pintype "passive"))
      (node (ref "C15") (pin "2") (pinfunction "2_2") (pintype "passive"))
      (node (ref "C16") (pin "2") (pinfunction "2_2") (pintype "passive"))
      (node (ref "C17") (pin "1") (pinfunction "1_1") (pintype "passive"))
      (node (ref "C18") (pin "1") (pinfunction "1_1") (pintype "passive"))
      (node (ref "C19") (pin "2") (pinfunction "2_2") (pintype "passive"))
      (node (ref "C2") (pin "2") (pinfunction "2_2") (pintype "passive"))
      (node (ref "C20") (pin "2") (pinfunction "2_2") (pintype "passive"))
      (node (ref "C21") (pin "2") (pinfunction "2_2") (pintype "passive"))
      (node (ref "C22") (pin "2") (pinfunction "2_2") (pintype "passive"))
      (node (ref "C23") (pin "1") (pinfunction "1_1") (pintype "passive"))
      (node (ref "C24") (pin "1") (pinfunction "1_1") (pintype "passive"))
      (node (ref "C25") (pin "2") (pinfunction "2_2") (pintype "passive"))
      (node (ref "C27") (pin "1") (pinfunction "1_1") (pintype "passive"))
      (node (ref "C29") (pin "1") (pinfunction "1_1") (pintype "passive"))
      (node (ref "C3") (pin "2") (pinfunction "2_2") (pintype "passive"))
      (node (ref "C30") (pin "1") (pinfunction "1_1") (pintype "passive"))
      (node (ref "C31") (pin "1") (pinfunction "1_1") (pintype "passive"))
      (node (ref "C32") (pin "1") (pinfunction "1_1") (pintype "passive"))
      (node (ref "C33") (pin "2") (pinfunction "2_2") (pintype "passive"))
      (node (ref "C34") (pin "1") (pinfunction "1_1") (pintype "passive"))
      (node (ref "C37") (pin "1") (pinfunction "1_1") (pintype "passive"))
      (node (ref "C38") (pin "1") (pinfunction "1_1") (pintype "passive"))
      (node (ref "C39") (pin "2") (pinfunction "2_2") (pintype "passive"))
      (node (ref "C4") (pin "2") (pinfunction "2_2") (pintype "passive"))
      (node (ref "C42") (pin "2") (pinfunction "2_2") (pintype "passive"))
      (node (ref "C43") (pin "2") (pinfunction "2_2") (pintype "passive"))
      (node (ref "C5") (pin "2") (pinfunction "2_2") (pintype "passive"))
      (node (ref "C6") (pin "2") (pinfunction "2_2") (pintype "passive"))
      (node (ref "C7") (pin "2") (pinfunction "2_2") (pintype "passive"))
      (node (ref "C8") (pin "2") (pinfunction "2_2") (pintype "passive"))
      (node (ref "C9") (pin "2") (pinfunction "2_2") (pintype "passive"))
      (node (ref "D3") (pin "2") (pinfunction "GND_2") (pintype "bidirectional"))
      (node (ref "D4") (pin "1") (pinfunction "K_1") (pintype "bidirectional"))
      (node (ref "EPD_C1") (pin "1") (pinfunction "1_1") (pintype "passive"))
      (node (ref "EPD_C10") (pin "1") (pinfunction "1_1") (pintype "passive"))
      (node (ref "EPD_C11") (pin "1") (pinfunction "1_1") (pintype "passive"))
      (node (ref "EPD_C12") (pin "1") (pinfunction "1_1") (pintype "passive"))
      (node (ref "EPD_C2") (pin "1") (pinfunction "1_1") (pintype "passive"))
      (node (ref "EPD_C5") (pin "2") (pinfunction "2_2") (pintype "passive"))
      (node (ref "EPD_C6") (pin "1") (pinfunction "1_1") (pintype "passive"))
      (node (ref "EPD_C7") (pin "1") (pinfunction "1_1") (pintype "passive"))
      (node (ref "EPD_C8") (pin "1") (pinfunction "1_1") (pintype "passive"))
      (node (ref "EPD_C9") (pin "1") (pinfunction "1_1") (pintype "passive"))
      (node (ref "IC1") (pin "D2") (pinfunction "GND_D2") (pintype "bidirectional"))
      (node (ref "IC2") (pin "B1") (pinfunction "IN/TRIG_B1") (pintype "bidirectional"))
      (node (ref "IC2") (pin "B3") (pinfunction "GND_B3") (pintype "bidirectional"))
      (node (ref "IC3") (pin "8") (pinfunction "GNDIO_8") (pintype "bidirectional"))
      (node (ref "IC3") (pin "9") (pinfunction "GND_9") (pintype "bidirectional"))
      (node (ref "IC9") (pin "B1") (pinfunction "VSEL_B1") (pintype "bidirectional"))
      (node (ref "IC9") (pin "C1") (pinfunction "AGND_C1") (pintype "bidirectional"))
      (node (ref "IC9") (pin "C2") (pinfunction "PGND_1_C2") (pintype "bidirectional"))
      (node (ref "IC9") (pin "C3") (pinfunction "PGND_2_C3") (pintype "bidirectional"))
      (node (ref "J1") (pin "17") (pinfunction "17_17") (pintype "bidirectional"))
      (node (ref "J1") (pin "8") (pinfunction "8_8") (pintype "bidirectional"))
      (node (ref "J1") (pin "MP1") (pinfunction "MP1_MP1") (pintype "bidirectional"))
      (node (ref "J1") (pin "MP2") (pinfunction "MP2_MP2") (pintype "bidirectional"))
      (node (ref "J2") (pin "3") (pinfunction "3_3") (pintype "bidirectional"))
      (node (ref "J2") (pin "5") (pinfunction "5_5") (pintype "bidirectional"))
      (node (ref "J4") (pin "A12_B1") (pinfunction "GND_A12_B1") (pintype "power_in"))
      (node (ref "J4") (pin "A1_B12") (pinfunction "GND_A1_B12") (pintype "power_in"))
      (node (ref "J4") (pin "SH1") (pinfunction "SHIELD_SH1") (pintype "passive"))
      (node (ref "J4") (pin "SH2") (pinfunction "SHIELD_SH2") (pintype "passive"))
      (node (ref "J4") (pin "SH3") (pinfunction "SHIELD_SH3") (pintype "passive"))
      (node (ref "J4") (pin "SH4") (pinfunction "SHIELD_SH4") (pintype "passive"))
      (node (ref "R1_USB") (pin "1") (pinfunction "1_1") (pintype "bidirectional"))
      (node (ref "R2_EP_DR") (pin "1") (pinfunction "1_1") (pintype "bidirectional"))
      (node (ref "R2_USB") (pin "2") (pinfunction "2_2") (pintype "bidirectional"))
      (node (ref "R3") (pin "1") (pinfunction "1_1") (pintype "bidirectional"))
      (node (ref "R9") (pin "1") (pinfunction "1_1") (pintype "bidirectional"))
      (node (ref "R_TYPE_SEL") (pin "1") (pinfunction "1_1") (pintype "bidirectional"))
      (node (ref "SJ1") (pin "1") (pinfunction "1_1") (pintype "passive"))
      (node (ref "SW_DN") (pin "1") (pinfunction "1_1") (pintype "passive"))
      (node (ref "SW_ENT") (pin "1") (pinfunction "1_1") (pintype "passive"))
      (node (ref "SW_UP") (pin "1") (pinfunction "1_1") (pintype "passive"))
      (node (ref "TP_BAT_GND") (pin "TP") (pinfunction "TP_TP") (pintype "input"))
      (node (ref "TP_GND") (pin "TP") (pinfunction "TP_TP") (pintype "input"))
      (node (ref "U$3") (pin "2") (pinfunction "2_2") (pintype "passive"))
      (node (ref "U1") (pin "P$74") (pinfunction "VSS_PAD_P$74") (pintype "bidirectional"))
      (node (ref "U1") (pin "P$75") (pinfunction "VSS_PAD_P$75") (pintype "bidirectional"))
      (node (ref "U1") (pin "P$76") (pinfunction "VSS_PAD_P$76") (pintype "bidirectional"))
      (node (ref "U1") (pin "P$77") (pinfunction "VSS_PAD_P$77") (pintype "bidirectional"))
      (node (ref "U1") (pin "P$78") (pinfunction "VSS_PAD_P$78") (pintype "bidirectional"))
      (node (ref "U1") (pin "P$79") (pinfunction "VSS_PAD_P$79") (pintype "bidirectional"))
      (node (ref "U1") (pin "P$80") (pinfunction "VSS_PAD_P$80") (pintype "bidirectional"))
      (node (ref "U1") (pin "P$81") (pinfunction "VSS_PAD_P$81") (pintype "bidirectional"))
      (node (ref "U1") (pin "P$82") (pinfunction "VSS_PAD_P$82") (pintype "bidirectional"))
      (node (ref "U1") (pin "P$83") (pinfunction "VSS_PAD_P$83") (pintype "bidirectional"))
      (node (ref "U1") (pin "P$84") (pinfunction "VSS_PAD_P$84") (pintype "bidirectional"))
      (node (ref "U1") (pin "P$85") (pinfunction "VSS_PAD_P$85") (pintype "bidirectional"))
      (node (ref "U1") (pin "P$86") (pinfunction "VSS_PAD_P$86") (pintype "bidirectional"))
      (node (ref "U1") (pin "P$87") (pinfunction "VSS_PAD_P$87") (pintype "bidirectional"))
      (node (ref "U1") (pin "P$88") (pinfunction "VSS_PAD_P$88") (pintype "bidirectional"))
      (node (ref "U1") (pin "P$89") (pinfunction "VSS_PAD_P$89") (pintype "bidirectional"))
      (node (ref "U1") (pin "P$90") (pinfunction "VSS_PAD_P$90") (pintype "bidirectional"))
      (node (ref "U1") (pin "P$B7") (pinfunction "VSS_P$B7") (pintype "power_in"))
      (node (ref "U1") (pin "P$F23") (pinfunction "VSS_PA_P$F23") (pintype "bidirectional"))
      (node (ref "U3") (pin "1") (pinfunction "CTG_1") (pintype "power_in"))
      (node (ref "U3") (pin "4") (pinfunction "GND_4") (pintype "power_in"))
      (node (ref "U3") (pin "6") (pinfunction "QSTRT_6") (pintype "input"))
      (node (ref "U3") (pin "9") (pinfunction "EP_9") (pintype "power_in"))
      (node (ref "X1") (pin "2") (pinfunction "2_2") (pintype "passive"))
      (node (ref "X1") (pin "4") (pinfunction "4_4") (pintype "passive"))
    )
    (net (code "17") (name "HAPTIC_EN") (class "Default")
      (node (ref "IC2") (pin "A1") (pinfunction "EN_A1") (pintype "bidirectional"))
      (node (ref "U1") (pin "P$U1") (pinfunction "P0.12_P$U1") (pintype "bidirectional"))
    )
    (net (code "18") (name "IMU_INT1") (class "Default")
      (node (ref "IC3") (pin "5") (pinfunction "INT1_5") (pintype "bidirectional"))
      (node (ref "U1") (pin "P$N1") (pinfunction "P0.08_P$N1") (pintype "bidirectional"))
    )
    (net (code "19") (name "IMU_INT2") (class "Default")
      (node (ref "IC3") (pin "6") (pinfunction "INT2_6") (pintype "bidirectional"))
      (node (ref "U1") (pin "P$P2") (pinfunction "P1.08_P$P2") (pintype "bidirectional"))
    )
    (net (code "20") (name "LX1") (class "Default")
      (node (ref "IC9") (pin "B2") (pinfunction "SW1_1_B2") (pintype "bidirectional"))
      (node (ref "IC9") (pin "B3") (pinfunction "SW1_2_B3") (pintype "bidirectional"))
      (node (ref "L7") (pin "1") (pinfunction "1_1") (pintype "bidirectional"))
    )
    (net (code "21") (name "LX2") (class "Default")
      (node (ref "IC9") (pin "D2") (pinfunction "SW2_1_D2") (pintype "bidirectional"))
      (node (ref "IC9") (pin "D3") (pinfunction "SW2_2_D3") (pintype "bidirectional"))
      (node (ref "L7") (pin "2") (pinfunction "2_2") (pintype "bidirectional"))
    )
    (net (code "22") (name "MOSI") (class "Default")
      (node (ref "J1") (pin "14") (pinfunction "14_14") (pintype "bidirectional"))
      (node (ref "U1") (pin "P$B13") (pinfunction "P0.03/AIN1_P$B13") (pintype "bidirectional"))
    )
    (net (code "23") (name "Net-(D2-K)") (class "Default")
      (node (ref "C2-EP-DR") (pin "1") (pinfunction "1_1") (pintype "passive"))
      (node (ref "D2") (pin "1") (pinfunction "K_1") (pintype "bidirectional"))
      (node (ref "D4") (pin "2") (pinfunction "A_2") (pintype "bidirectional"))
    )
    (net (code "24") (name "Net-(D5-A)") (class "Default")
      (node (ref "C2-EP-DR") (pin "2") (pinfunction "2_2") (pintype "passive"))
      (node (ref "D5") (pin "2") (pinfunction "A_2") (pintype "bidirectional"))
      (node (ref "L5") (pin "1") (pinfunction "1_1") (pintype "passive"))
      (node (ref "Q3") (pin "3") (pinfunction "D_3") (pintype "bidirectional"))
    )
    (net (code "25") (name "Net-(EPD_C1-Pad2)") (class "Default")
      (node (ref "EPD_C1") (pin "2") (pinfunction "2_2") (pintype "passive"))
      (node (ref "J1") (pin "5") (pinfunction "5_5") (pintype "bidirectional"))
    )
    (net (code "26") (name "Net-(EPD_C2-Pad2)") (class "Default")
      (node (ref "EPD_C2") (pin "2") (pinfunction "2_2") (pintype "passive"))
      (node (ref "J1") (pin "4") (pinfunction "4_4") (pintype "bidirectional"))
    )
    (net (code "27") (name "Net-(EPD_C6-Pad2)") (class "Default")
      (node (ref "EPD_C6") (pin "2") (pinfunction "2_2") (pintype "passive"))
      (node (ref "J1") (pin "18") (pinfunction "18_18") (pintype "bidirectional"))
    )
    (net (code "28") (name "Net-(EPD_C7-Pad2)") (class "Default")
      (node (ref "EPD_C7") (pin "2") (pinfunction "2_2") (pintype "passive"))
      (node (ref "J1") (pin "19") (pinfunction "19_19") (pintype "bidirectional"))
    )
    (net (code "29") (name "Net-(EPD_C8-Pad2)") (class "Default")
      (node (ref "EPD_C8") (pin "2") (pinfunction "2_2") (pintype "passive"))
      (node (ref "J1") (pin "20") (pinfunction "20_20") (pintype "bidirectional"))
    )
    (net (code "30") (name "Net-(EPD_C10-Pad2)") (class "Default")
      (node (ref "EPD_C10") (pin "2") (pinfunction "2_2") (pintype "passive"))
      (node (ref "J1") (pin "22") (pinfunction "22_22") (pintype "bidirectional"))
    )
    (net (code "31") (name "Net-(EPD_C12-Pad2)") (class "Default")
      (node (ref "EPD_C12") (pin "2") (pinfunction "2_2") (pintype "passive"))
      (node (ref "J1") (pin "24") (pinfunction "24_24") (pintype "bidirectional"))
    )
    (net (code "32") (name "Net-(IC1-TS{slash}MR)") (class "Default")
      (node (ref "IC1") (pin "D1") (pinfunction "TS/MR_D1") (pintype "bidirectional"))
      (node (ref "R9") (pin "2") (pinfunction "2_2") (pintype "bidirectional"))
    )
    (net (code "33") (name "Net-(IC2-REG)") (class "Default")
      (node (ref "C32") (pin "2") (pinfunction "2_2") (pintype "passive"))
      (node (ref "IC2") (pin "A2") (pinfunction "REG_A2") (pintype "bidirectional"))
    )
    (net (code "34") (name "Net-(IC3-SDO)") (class "Default")
      (node (ref "IC3") (pin "1") (pinfunction "SDO_1") (pintype "bidirectional"))
      (node (ref "R3") (pin "2") (pinfunction "2_2") (pintype "bidirectional"))
    )
    (net (code "35") (name "Net-(IC9-SCL)") (class "Default")
      (node (ref "IC9") (pin "D1") (pinfunction "SCL_D1") (pintype "bidirectional"))
      (node (ref "R4") (pin "2") (pinfunction "2_2") (pintype "bidirectional"))
    )
    (net (code "36") (name "Net-(IC9-SDA)") (class "Default")
      (node (ref "IC9") (pin "E1") (pinfunction "SDA_E1") (pintype "bidirectional"))
      (node (ref "R2") (pin "2") (pinfunction "2_2") (pintype "bidirectional"))
    )
    (net (code "37") (name "Net-(J4-CC1)") (class "Default")
      (node (ref "J4") (pin "A5") (pinfunction "CC1_A5") (pintype "bidirectional"))
      (node (ref "R1_USB") (pin "2") (pinfunction "2_2") (pintype "bidirectional"))
    )
    (net (code "38") (name "Net-(J4-CC2)") (class "Default")
      (node (ref "J4") (pin "B5") (pinfunction "CC2_B5") (pintype "bidirectional"))
      (node (ref "R2_USB") (pin "1") (pinfunction "1_1") (pintype "bidirectional"))
    )
    (net (code "39") (name "Net-(L2-Pad2)") (class "Default")
      (node (ref "L2") (pin "2") (pinfunction "2_2") (pintype "passive"))
      (node (ref "L3") (pin "1") (pinfunction "1_1") (pintype "passive"))
    )
    (net (code "40") (name "Net-(R1_EP_DR-Pad1)") (class "Default")
      (node (ref "R1_EP_DR") (pin "1") (pinfunction "1_1") (pintype "bidirectional"))
      (node (ref "R_TYPE_SEL") (pin "2") (pinfunction "2_2") (pintype "bidirectional"))
      (node (ref "SJ1") (pin "2") (pinfunction "2_2") (pintype "passive"))
    )
    (net (code "41") (name "Net-(U1-ANT)") (class "Default")
      (node (ref "C3") (pin "1") (pinfunction "1_1") (pintype "passive"))
      (node (ref "L1") (pin "1") (pinfunction "1_1") (pintype "passive"))
      (node (ref "U1") (pin "P$H23") (pinfunction "ANT_P$H23") (pintype "bidirectional"))
    )
    (net (code "42") (name "Net-(U1-DCC)") (class "Default")
      (node (ref "L2") (pin "1") (pinfunction "1_1") (pintype "passive"))
      (node (ref "U1") (pin "P$B3") (pinfunction "DCC_P$B3") (pintype "output"))
    )
    (net (code "43") (name "Net-(U1-DEC2)") (class "Default")
      (node (ref "C13") (pin "1") (pinfunction "1_1") (pintype "passive"))
      (node (ref "U1") (pin "P$A18") (pinfunction "DEC2_P$A18") (pintype "bidirectional"))
    )
    (net (code "44") (name "Net-(U1-DEC3V3)") (class "Default")
      (node (ref "C20") (pin "1") (pinfunction "1_1") (pintype "passive"))
      (node (ref "U1") (pin "P$AC5") (pinfunction "DEC3V3_P$AC5") (pintype "bidirectional"))
    )
    (net (code "45") (name "Net-(U1-DEC5)") (class "Default")
      (node (ref "C9") (pin "1") (pinfunction "1_1") (pintype "passive"))
      (node (ref "U1") (pin "P$N24") (pinfunction "DEC5_P$N24") (pintype "bidirectional"))
    )
    (net (code "46") (name "Net-(U1-XC1)") (class "Default")
      (node (ref "C1") (pin "1") (pinfunction "1_1") (pintype "passive"))
      (node (ref "U1") (pin "P$B24") (pinfunction "XC1_P$B24") (pintype "input"))
      (node (ref "X1") (pin "1") (pinfunction "1_1") (pintype "passive"))
    )
    (net (code "47") (name "Net-(U1-XC2)") (class "Default")
      (node (ref "C2") (pin "1") (pinfunction "1_1") (pintype "passive"))
      (node (ref "U1") (pin "P$A23") (pinfunction "XC2_P$A23") (pintype "output"))
      (node (ref "X1") (pin "3") (pinfunction "3_3") (pintype "passive"))
    )
    (net (code "48") (name "OUT+") (class "Default")
      (node (ref "IC2") (pin "A3") (pinfunction "OUT+_A3") (pintype "bidirectional"))
      (node (ref "TP_OP") (pin "TP") (pinfunction "TP_TP") (pintype "input"))
    )
    (net (code "49") (name "OUT-") (class "Default")
      (node (ref "IC2") (pin "C3") (pinfunction "OUT-_C3") (pintype "bidirectional"))
      (node (ref "TP_ON") (pin "TP") (pinfunction "TP_TP") (pintype "input"))
    )
    (net (code "50") (name "P0.00{slash}XL1") (class "Default")
      (node (ref "C17") (pin "2") (pinfunction "2_2") (pintype "passive"))
      (node (ref "U1") (pin "P$D2") (pinfunction "P0.00/XL1_P$D2") (pintype "bidirectional"))
      (node (ref "X2") (pin "1") (pinfunction "1_1") (pintype "passive"))
    )
    (net (code "51") (name "P0.01{slash}XL2") (class "Default")
      (node (ref "C18") (pin "2") (pinfunction "2_2") (pintype "passive"))
      (node (ref "U1") (pin "P$F2") (pinfunction "P0.01/XL2_P$F2") (pintype "bidirectional"))
      (node (ref "X2") (pin "2") (pinfunction "2_2") (pintype "passive"))
    )
    (net (code "52") (name "P0.04") (class "Default")
      (node (ref "U1") (pin "P$J1") (pinfunction "P0.04/AIN2_P$J1") (pintype "bidirectional"))
    )
    (net (code "53") (name "P0.09") (class "Default")
      (node (ref "U1") (pin "P$L24") (pinfunction "P0.09/NFC1_P$L24") (pintype "bidirectional"))
    )
    (net (code "54") (name "P0.13") (class "Default")
      (node (ref "C30") (pin "2") (pinfunction "2_2") (pintype "passive"))
      (node (ref "R5") (pin "1") (pinfunction "1_1") (pintype "bidirectional"))
      (node (ref "SW_UP") (pin "2") (pinfunction "2_2") (pintype "passive"))
      (node (ref "U1") (pin "P$AD8") (pinfunction "P0.13_P$AD8") (pintype "bidirectional"))
    )
    (net (code "55") (name "P0.14") (class "Default")
      (node (ref "C31") (pin "2") (pinfunction "2_2") (pintype "passive"))
      (node (ref "R8") (pin "1") (pinfunction "1_1") (pintype "bidirectional"))
      (node (ref "SW_ENT") (pin "2") (pinfunction "2_2") (pintype "passive"))
      (node (ref "U1") (pin "P$AC9") (pinfunction "P0.14_P$AC9") (pintype "bidirectional"))
    )
    (net (code "56") (name "P0.19") (class "Default")
      (node (ref "U1") (pin "P$AC15") (pinfunction "P0.19_P$AC15") (pintype "bidirectional"))
    )
    (net (code "57") (name "P0.20") (class "Default")
      (node (ref "U1") (pin "P$AD16") (pinfunction "P0.20_P$AD16") (pintype "bidirectional"))
    )
    (net (code "58") (name "P0.21") (class "Default")
      (node (ref "U1") (pin "P$AC17") (pinfunction "P0.21_P$AC17") (pintype "bidirectional"))
    )
    (net (code "59") (name "P0.22") (class "Default")
      (node (ref "U1") (pin "P$AD18") (pinfunction "P0.22_P$AD18") (pintype "bidirectional"))
    )
    (net (code "60") (name "P0.23") (class "Default")
      (node (ref "U1") (pin "P$AC19") (pinfunction "P0.23_P$AC19") (pintype "bidirectional"))
    )
    (net (code "61") (name "P0.24") (class "Default")
      (node (ref "U1") (pin "P$AD20") (pinfunction "P0.24_P$AD20") (pintype "bidirectional"))
    )
    (net (code "62") (name "P0.25") (class "Default")
      (node (ref "U1") (pin "P$AC21") (pinfunction "P0.25_P$AC21") (pintype "bidirectional"))
    )
    (net (code "63") (name "P0.26") (class "Default")
      (node (ref "U1") (pin "P$G1") (pinfunction "P0.26_P$G1") (pintype "bidirectional"))
    )
    (net (code "64") (name "P0.27") (class "Default")
      (node (ref "U1") (pin "P$H2") (pinfunction "P0.27_P$H2") (pintype "bidirectional"))
    )
    (net (code "65") (name "P0.28") (class "Default")
      (node (ref "U1") (pin "P$B11") (pinfunction "P0.28/AIN4_P$B11") (pintype "bidirectional"))
    )
    (net (code "66") (name "P0.29") (class "Default")
      (node (ref "U1") (pin "P$A10") (pinfunction "P0.29/AIN5_P$A10") (pintype "bidirectional"))
    )
    (net (code "67") (name "P0.30") (class "Default")
      (node (ref "U1") (pin "P$B9") (pinfunction "P0.30/AIN6_P$B9") (pintype "bidirectional"))
    )
    (net (code "68") (name "P0.31") (class "Default")
      (node (ref "U1") (pin "P$A8") (pinfunction "P0.31/AIN7_P$A8") (pintype "bidirectional"))
    )
    (net (code "69") (name "P1.01") (class "Default")
      (node (ref "DMG2305UX-7") (pin "1") (pinfunction "G_1") (pintype "bidirectional"))
      (node (ref "R_PWR_EPD") (pin "1") (pinfunction "1_1") (pintype "bidirectional"))
      (node (ref "U1") (pin "P$Y23") (pinfunction "P1.01_P$Y23") (pintype "bidirectional"))
    )
    (net (code "70") (name "P1.02") (class "Default")
      (node (ref "C29") (pin "2") (pinfunction "2_2") (pintype "passive"))
      (node (ref "R7") (pin "1") (pinfunction "1_1") (pintype "bidirectional"))
      (node (ref "SW_DN") (pin "2") (pinfunction "2_2") (pintype "passive"))
      (node (ref "U1") (pin "P$W24") (pinfunction "P1.02_P$W24") (pintype "bidirectional"))
    )
    (net (code "71") (name "P1.03") (class "Default")
      (node (ref "U1") (pin "P$V23") (pinfunction "P1.03_P$V23") (pintype "bidirectional"))
    )
    (net (code "72") (name "P1.04") (class "Default")
      (node (ref "U1") (pin "P$U24") (pinfunction "P1.04_P$U24") (pintype "bidirectional"))
    )
    (net (code "73") (name "P1.05") (class "Default")
      (node (ref "U1") (pin "P$T23") (pinfunction "P1.05_P$T23") (pintype "bidirectional"))
    )
    (net (code "74") (name "P1.06") (class "Default")
      (node (ref "U1") (pin "P$R24") (pinfunction "P1.06_P$R24") (pintype "bidirectional"))
    )
    (net (code "75") (name "P1.07") (class "Default")
      (node (ref "U1") (pin "P$P23") (pinfunction "P1.07_P$P23") (pintype "bidirectional"))
    )
    (net (code "76") (name "P1.09") (class "Default")
      (node (ref "U1") (pin "P$R1") (pinfunction "P1.09_P$R1") (pintype "bidirectional"))
    )
    (net (code "77") (name "P1.10") (class "Default")
      (node (ref "U1") (pin "P$A20") (pinfunction "P1.10_P$A20") (pintype "bidirectional"))
    )
    (net (code "78") (name "P1.11") (class "Default")
      (node (ref "U1") (pin "P$B19") (pinfunction "P1.11_P$B19") (pintype "bidirectional"))
    )
    (net (code "79") (name "P1.12") (class "Default")
      (node (ref "U1") (pin "P$B17") (pinfunction "P1.12_P$B17") (pintype "bidirectional"))
    )
    (net (code "80") (name "P1.13") (class "Default")
      (node (ref "U1") (pin "P$A16") (pinfunction "P1.13_P$A16") (pintype "bidirectional"))
    )
    (net (code "81") (name "P1.14") (class "Default")
      (node (ref "U1") (pin "P$B15") (pinfunction "P1.14_P$B15") (pintype "bidirectional"))
    )
    (net (code "82") (name "P1.15") (class "Default")
      (node (ref "U1") (pin "P$A14") (pinfunction "P1.15_P$A14") (pintype "bidirectional"))
    )
    (net (code "83") (name "PMIC_INT") (class "Default")
      (node (ref "IC1") (pin "A1") (pinfunction "~{INT}_A1") (pintype "bidirectional"))
      (node (ref "U1") (pin "P$T2") (pinfunction "P0.11_P$T2") (pintype "bidirectional"))
    )
    (net (code "84") (name "PREVGH") (class "Default")
      (node (ref "D5") (pin "1") (pinfunction "K_1") (pintype "bidirectional"))
      (node (ref "EPD_C9") (pin "2") (pinfunction "2_2") (pintype "passive"))
      (node (ref "J1") (pin "21") (pinfunction "21_21") (pintype "bidirectional"))
    )
    (net (code "85") (name "PREVGL") (class "Default")
      (node (ref "D2") (pin "2") (pinfunction "A_2") (pintype "bidirectional"))
      (node (ref "EPD_C11") (pin "2") (pinfunction "2_2") (pintype "passive"))
      (node (ref "J1") (pin "23") (pinfunction "23_23") (pintype "bidirectional"))
    )
    (net (code "86") (name "RESE") (class "Default")
      (node (ref "J1") (pin "3") (pinfunction "3_3") (pintype "bidirectional"))
      (node (ref "Q3") (pin "2") (pinfunction "S_2") (pintype "bidirectional"))
      (node (ref "R1_EP_DR") (pin "2") (pinfunction "2_2") (pintype "bidirectional"))
    )
    (net (code "87") (name "RESET") (class "Default")
      (node (ref "J2") (pin "6") (pinfunction "6_6") (pintype "bidirectional"))
      (node (ref "TP_RESET") (pin "TP") (pinfunction "TP_TP") (pintype "input"))
      (node (ref "U1") (pin "P$AC13") (pinfunction "P0.18/RESET_P$AC13") (pintype "bidirectional"))
    )
    (net (code "88") (name "RF") (class "Default")
      (node (ref "ANT1") (pin "1") (pinfunction "FEED_1") (pintype "input"))
      (node (ref "C22") (pin "1") (pinfunction "1_1") (pintype "passive"))
      (node (ref "C4") (pin "1") (pinfunction "1_1") (pintype "passive"))
      (node (ref "L1") (pin "2") (pinfunction "2_2") (pintype "passive"))
    )
    (net (code "89") (name "SCK") (class "Default")
      (node (ref "J1") (pin "13") (pinfunction "13_13") (pintype "bidirectional"))
      (node (ref "U1") (pin "P$A12") (pinfunction "P0.02/AIN0_P$A12") (pintype "bidirectional"))
    )
    (net (code "90") (name "SCL") (class "Default")
      (node (ref "IC1") (pin "B1") (pinfunction "SCL_B1") (pintype "bidirectional"))
      (node (ref "IC2") (pin "C1") (pinfunction "SCL_C1") (pintype "bidirectional"))
      (node (ref "IC3") (pin "12") (pinfunction "SCX_12") (pintype "bidirectional"))
      (node (ref "R17") (pin "2") (pinfunction "2_2") (pintype "bidirectional"))
      (node (ref "R4") (pin "1") (pinfunction "1_1") (pintype "bidirectional"))
      (node (ref "TP_SCL") (pin "TP") (pinfunction "TP_TP") (pintype "input"))
      (node (ref "U1") (pin "P$M2") (pinfunction "P0.07_P$M2") (pintype "bidirectional"))
      (node (ref "U3") (pin "7") (pinfunction "SCL_7") (pintype "input"))
    )
    (net (code "91") (name "SDA") (class "Default")
      (node (ref "IC1") (pin "C1") (pinfunction "SDA_C1") (pintype "bidirectional"))
      (node (ref "IC2") (pin "B2") (pinfunction "SDA_B2") (pintype "bidirectional"))
      (node (ref "IC3") (pin "2") (pinfunction "SDX_2") (pintype "bidirectional"))
      (node (ref "R18") (pin "2") (pinfunction "2_2") (pintype "bidirectional"))
      (node (ref "R2") (pin "1") (pinfunction "1_1") (pintype "bidirectional"))
      (node (ref "TP_SDA") (pin "TP") (pinfunction "TP_TP") (pintype "input"))
      (node (ref "U1") (pin "P$L1") (pinfunction "P0.06_P$L1") (pintype "bidirectional"))
      (node (ref "U3") (pin "8") (pinfunction "SDA_8") (pintype "bidirectional"))
    )
    (net (code "92") (name "SWDCLK") (class "Default")
      (node (ref "J2") (pin "4") (pinfunction "4_4") (pintype "bidirectional"))
      (node (ref "TP_SWDCLK") (pin "TP") (pinfunction "TP_TP") (pintype "input"))
      (node (ref "U1") (pin "P$AA24") (pinfunction "SWDCLK_P$AA24") (pintype "input"))
    )
    (net (code "93") (name "SWDIO") (class "Default")
      (node (ref "J2") (pin "2") (pinfunction "2_2") (pintype "bidirectional"))
      (node (ref "TP_SWDIO") (pin "TP") (pinfunction "TP_TP") (pintype "input"))
      (node (ref "U1") (pin "P$AC24") (pinfunction "SWDIO_P$AC24") (pintype "bidirectional"))
    )
    (net (code "94") (name "SWO") (class "Default")
      (node (ref "TP_SWO") (pin "TP") (pinfunction "TP_TP") (pintype "input"))
      (node (ref "U1") (pin "P$AD22") (pinfunction "P1.00_P$AD22") (pintype "bidirectional"))
    )
    (net (code "95") (name "VBAT") (class "Default")
      (node (ref "C27") (pin "2") (pinfunction "2_2") (pintype "passive"))
      (node (ref "C37") (pin "2") (pinfunction "2_2") (pintype "passive"))
      (node (ref "IC1") (pin "C2") (pinfunction "BAT_C2") (pintype "bidirectional"))
      (node (ref "TP_VBAT") (pin "TP") (pinfunction "TP_TP") (pintype "input"))
      (node (ref "U3") (pin "2") (pinfunction "CELL_2") (pintype "power_in"))
      (node (ref "U3") (pin "3") (pinfunction "VDD_3") (pintype "power_in"))
    )
    (net (code "96") (name "VBUS") (class "Default")
      (node (ref "C21") (pin "1") (pinfunction "1_1") (pintype "passive"))
      (node (ref "C38") (pin "2") (pinfunction "2_2") (pintype "passive"))
      (node (ref "C42") (pin "1") (pinfunction "1_1") (pintype "passive"))
      (node (ref "C43") (pin "1") (pinfunction "1_1") (pintype "passive"))
      (node (ref "D3") (pin "5") (pinfunction "VBUS_5") (pintype "bidirectional"))
      (node (ref "IC1") (pin "A2") (pinfunction "IN_A2") (pintype "bidirectional"))
      (node (ref "J4") (pin "A4_B9") (pinfunction "VBUS_A4_B9") (pintype "power_in"))
      (node (ref "J4") (pin "A9_B4") (pinfunction "VBUS_A9_B4") (pintype "power_in"))
      (node (ref "U1") (pin "P$AD2") (pinfunction "VBUS_P$AD2") (pintype "power_in"))
    )
    (net (code "97") (name "VREG") (class "Default")
      (node (ref "C23") (pin "2") (pinfunction "2_2") (pintype "passive"))
      (node (ref "C24") (pin "2") (pinfunction "2_2") (pintype "passive"))
      (node (ref "C39") (pin "1") (pinfunction "1_1") (pintype "passive"))
      (node (ref "IC1") (pin "B2") (pinfunction "SYS_B2") (pintype "bidirectional"))
      (node (ref "IC9") (pin "A1") (pinfunction "EN_A1") (pintype "bidirectional"))
      (node (ref "IC9") (pin "A2") (pinfunction "VIN_1_A2") (pintype "bidirectional"))
      (node (ref "IC9") (pin "A3") (pinfunction "VIN_2_A3") (pintype "bidirectional"))
      (node (ref "TP_VREG") (pin "TP") (pinfunction "TP_TP") (pintype "input"))
      (node (ref "U$3") (pin "1") (pinfunction "1_1") (pintype "passive"))
    )
    (net (code "98") (name "unconnected-(ANT1-NC-Pad2)") (class "Default")
      (node (ref "ANT1") (pin "2") (pinfunction "NC_2") (pintype "no_connect"))
    )
    (net (code "99") (name "unconnected-(IC3-ASCL-Pad11)") (class "Default")
      (node (ref "IC3") (pin "11") (pinfunction "ASCL_11") (pintype "bidirectional"))
    )
    (net (code "100") (name "unconnected-(IC3-ASDA-Pad4)") (class "Default")
      (node (ref "IC3") (pin "4") (pinfunction "ASDA_4") (pintype "bidirectional"))
    )
    (net (code "101") (name "unconnected-(J1-Pad1)") (class "Default")
      (node (ref "J1") (pin "1") (pinfunction "1_1") (pintype "bidirectional"))
    )
    (net (code "102") (name "unconnected-(J1-Pad6)") (class "Default")
      (node (ref "J1") (pin "6") (pinfunction "6_6") (pintype "bidirectional"))
    )
    (net (code "103") (name "unconnected-(J1-Pad7)") (class "Default")
      (node (ref "J1") (pin "7") (pinfunction "7_7") (pintype "bidirectional"))
    )
    (net (code "104") (name "unconnected-(J4-SBU1-PadA8)") (class "Default")
      (node (ref "J4") (pin "A8") (pinfunction "SBU1_A8") (pintype "bidirectional"))
    )
    (net (code "105") (name "unconnected-(J4-SBU2-PadB8)") (class "Default")
      (node (ref "J4") (pin "B8") (pinfunction "SBU2_B8") (pintype "bidirectional"))
    )
    (net (code "106") (name "unconnected-(U1-DCCH-PadP$AB2)") (class "Default")
      (node (ref "U1") (pin "P$AB2") (pinfunction "DCCH_P$AB2") (pintype "bidirectional"))
    )
  )
)
